# 02_-MCU.net
KiCad netlist of a schematic drawn in Altium Designer
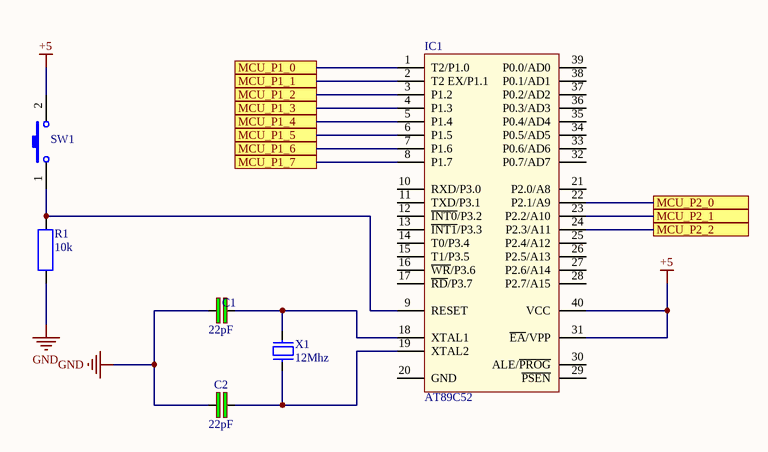
[diagram p0: [02]-MCU.SchDoc]

(export (version "E")
  (design (tool "Eeschema 10.0.6"))
  (components
    (comp (ref "C1")
      (value "22pF")
      (footprint "CAP_0805")
      (description "Cap SMD")
      (libsource (lib "My Library") (part "C"))
    )
    (comp (ref "C2")
      (value "22pF")
      (footprint "CAP_0805")
      (description "Cap SMD")
      (libsource (lib "My Library") (part "C"))
    )
    (comp (ref "IC1")
      (value "AT89C52")
      (footprint "DIP40/W0.6")
      (description "Atmel AT89C52, 8k Byte Flash Memory , 40 Pin")
      (libsource (lib "My Library") (part "AT89C52"))
    )
    (comp (ref "R1")
      (value "10k")
      (footprint "RES_SMD_0805")
      (description "Resistor 1W")
      (libsource (lib "My Library") (part "R1W"))
    )
    (comp (ref "SW1")
      (value "SW-2P-S")
      (footprint "SW-SMD")
      (description "Switch Small 2 Pin")
      (fields (field (name "PUBLISHER") "Altium Limited"))
      (libsource (lib "My Library") (part "SW-2PIN-SMALL"))
    )
    (comp (ref "X1")
      (value "12Mhz")
      (footprint "XT2")
      (description "Crystal For all Crystal 2pin.")
      (libsource (lib "My Library") (part "XT2"))
    )
  )
  (nets
    (net (code "1") (name "+5") (class "Default")
      (node (ref "IC1") (pin "31") (pinfunction "~{EA}/VPP_31") (pintype "passive"))
      (node (ref "IC1") (pin "40") (pinfunction "VCC_40") (pintype "power_in"))
      (node (ref "SW1") (pin "2") (pinfunction "2_2") (pintype "passive"))
    )
    (net (code "2") (name "/MCU_P1_0") (class "Default")
      (node (ref "IC1") (pin "1") (pinfunction "T2/P1.0_1") (pintype "passive"))
    )
    (net (code "3") (name "/MCU_P1_1") (class "Default")
      (node (ref "IC1") (pin "2") (pinfunction "T2_EX/P1.1_2") (pintype "passive"))
    )
    (net (code "4") (name "/MCU_P1_2") (class "Default")
      (node (ref "IC1") (pin "3") (pinfunction "P1.2_3") (pintype "passive"))
    )
    (net (code "5") (name "/MCU_P1_3") (class "Default")
      (node (ref "IC1") (pin "4") (pinfunction "P1.3_4") (pintype "passive"))
    )
    (net (code "6") (name "/MCU_P1_4") (class "Default")
      (node (ref "IC1") (pin "5") (pinfunction "P1.4_5") (pintype "passive"))
    )
    (net (code "7") (name "/MCU_P1_5") (class "Default")
      (node (ref "IC1") (pin "6") (pinfunction "P1.5_6") (pintype "passive"))
    )
    (net (code "8") (name "/MCU_P1_6") (class "Default")
      (node (ref "IC1") (pin "7") (pinfunction "P1.6_7") (pintype "passive"))
    )
    (net (code "9") (name "/MCU_P1_7") (class "Default")
      (node (ref "IC1") (pin "8") (pinfunction "P1.7_8") (pintype "passive"))
    )
    (net (code "10") (name "/MCU_P2_0") (class "Default")
      (node (ref "IC1") (pin "22") (pinfunction "P2.1/A9_22") (pintype "passive"))
    )
    (net (code "11") (name "/MCU_P2_1") (class "Default")
      (node (ref "IC1") (pin "23") (pinfunction "P2.2/A10_23") (pintype "passive"))
    )
    (net (code "12") (name "/MCU_P2_2") (class "Default")
      (node (ref "IC1") (pin "24") (pinfunction "P2.3/A11_24") (pintype "passive"))
    )
    (net (code "13") (name "GND") (class "Default")
      (node (ref "C1") (pin "1") (pinfunction "1_1") (pintype "passive"))
      (node (ref "C2") (pin "1") (pinfunction "1_1") (pintype "passive"))
      (node (ref "R1") (pin "1") (pinfunction "1_1") (pintype "passive"))
    )
    (net (code "14") (name "Net-(IC1-RESET)") (class "Default")
      (node (ref "IC1") (pin "9") (pinfunction "RESET_9") (pintype "passive"))
      (node (ref "R1") (pin "2") (pinfunction "2_2") (pintype "passive"))
      (node (ref "SW1") (pin "1") (pinfunction "1_1") (pintype "passive"))
    )
    (net (code "15") (name "Net-(IC1-XTAL1)") (class "Default")
      (node (ref "C1") (pin "2") (pinfunction "2_2") (pintype "passive"))
      (node (ref "IC1") (pin "18") (pinfunction "XTAL1_18") (pintype "passive"))
      (node (ref "X1") (pin "2") (pinfunction "2_2") (pintype "passive"))
    )
    (net (code "16") (name "Net-(IC1-XTAL2)") (class "Default")
      (node (ref "C2") (pin "2") (pinfunction "2_2") (pintype "passive"))
      (node (ref "IC1") (pin "19") (pinfunction "XTAL2_19") (pintype "passive"))
      (node (ref "X1") (pin "1") (pinfunction "1_1") (pintype "passive"))
    )
    (net (code "17") (name "unconnected-(IC1-ALE{slash}~{PROG}-Pad30)") (class "Default")
      (node (ref "IC1") (pin "30") (pinfunction "ALE/~{PROG}_30") (pintype "passive"))
    )
    (net (code "18") (name "unconnected-(IC1-GND-Pad20)") (class "Default")
      (node (ref "IC1") (pin "20") (pinfunction "GND_20") (pintype "open_emitter"))
    )
    (net (code "19") (name "unconnected-(IC1-P0.0{slash}AD0-Pad39)") (class "Default")
      (node (ref "IC1") (pin "39") (pinfunction "P0.0/AD0_39") (pintype "passive"))
    )
    (net (code "20") (name "unconnected-(IC1-P0.1{slash}AD1-Pad38)") (class "Default")
      (node (ref "IC1") (pin "38") (pinfunction "P0.1/AD1_38") (pintype "passive"))
    )
    (net (code "21") (name "unconnected-(IC1-P0.2{slash}AD2-Pad37)") (class "Default")
      (node (ref "IC1") (pin "37") (pinfunction "P0.2/AD2_37") (pintype "passive"))
    )
    (net (code "22") (name "unconnected-(IC1-P0.3{slash}AD3-Pad36)") (class "Default")
      (node (ref "IC1") (pin "36") (pinfunction "P0.3/AD3_36") (pintype "passive"))
    )
    (net (code "23") (name "unconnected-(IC1-P0.4{slash}AD4-Pad35)") (class "Default")
      (node (ref "IC1") (pin "35") (pinfunction "P0.4/AD4_35") (pintype "passive"))
    )
    (net (code "24") (name "unconnected-(IC1-P0.5{slash}AD5-Pad34)") (class "Default")
      (node (ref "IC1") (pin "34") (pinfunction "P0.5/AD5_34") (pintype "passive"))
    )
    (net (code "25") (name "unconnected-(IC1-P0.6{slash}AD6-Pad33)") (class "Default")
      (node (ref "IC1") (pin "33") (pinfunction "P0.6/AD6_33") (pintype "passive"))
    )
    (net (code "26") (name "unconnected-(IC1-P0.7{slash}AD7-Pad32)") (class "Default")
      (node (ref "IC1") (pin "32") (pinfunction "P0.7/AD7_32") (pintype "passive"))
    )
    (net (code "27") (name "unconnected-(IC1-P2.0{slash}A8-Pad21)") (class "Default")
      (node (ref "IC1") (pin "21") (pinfunction "P2.0/A8_21") (pintype "passive"))
    )
    (net (code "28") (name "unconnected-(IC1-P2.4{slash}A12-Pad25)") (class "Default")
      (node (ref "IC1") (pin "25") (pinfunction "P2.4/A12_25") (pintype "passive"))
    )
    (net (code "29") (name "unconnected-(IC1-P2.5{slash}A13-Pad26)") (class "Default")
      (node (ref "IC1") (pin "26") (pinfunction "P2.5/A13_26") (pintype "passive"))
    )
    (net (code "30") (name "unconnected-(IC1-P2.6{slash}A14-Pad27)") (class "Default")
      (node (ref "IC1") (pin "27") (pinfunction "P2.6/A14_27") (pintype "passive"))
    )
    (net (code "31") (name "unconnected-(IC1-P2.7{slash}A15-Pad28)") (class "Default")
      (node (ref "IC1") (pin "28") (pinfunction "P2.7/A15_28") (pintype "passive"))
    )
    (net (code "32") (name "unconnected-(IC1-RXD{slash}P3.0-Pad10)") (class "Default")
      (node (ref "IC1") (pin "10") (pinfunction "RXD/P3.0_10") (pintype "passive"))
    )
    (net (code "33") (name "unconnected-(IC1-T0{slash}P3.4-Pad14)") (class "Default")
      (node (ref "IC1") (pin "14") (pinfunction "T0/P3.4_14") (pintype "passive"))
    )
    (net (code "34") (name "unconnected-(IC1-T1{slash}P3.5-Pad15)") (class "Default")
      (node (ref "IC1") (pin "15") (pinfunction "T1/P3.5_15") (pintype "passive"))
    )
    (net (code "35") (name "unconnected-(IC1-TXD{slash}P3.1-Pad11)") (class "Default")
      (node (ref "IC1") (pin "11") (pinfunction "TXD/P3.1_11") (pintype "passive"))
    )
    (net (code "36") (name "unconnected-(IC1-~{INT0}{slash}P3.2-Pad12)") (class "Default")
      (node (ref "IC1") (pin "12") (pinfunction "~{INT0}/P3.2_12") (pintype "passive"))
    )
    (net (code "37") (name "unconnected-(IC1-~{INT1}{slash}P3.3-Pad13)") (class "Default")
      (node (ref "IC1") (pin "13") (pinfunction "~{INT1}/P3.3_13") (pintype "passive"))
    )
    (net (code "38") (name "unconnected-(IC1-~{PSEN}-Pad29)") (class "Default")
      (node (ref "IC1") (pin "29") (pinfunction "~{PSEN}_29") (pintype "passive"))
    )
    (net (code "39") (name "unconnected-(IC1-~{RD}{slash}P3.7-Pad17)") (class "Default")
      (node (ref "IC1") (pin "17") (pinfunction "~{RD}/P3.7_17") (pintype "passive"))
    )
    (net (code "40") (name "unconnected-(IC1-~{WR}{slash}P3.6-Pad16)") (class "Default")
      (node (ref "IC1") (pin "16") (pinfunction "~{WR}/P3.6_16") (pintype "passive"))
    )
  )
)
